# COM_SPI.net
KiCad netlist of a schematic drawn in Altium Designer
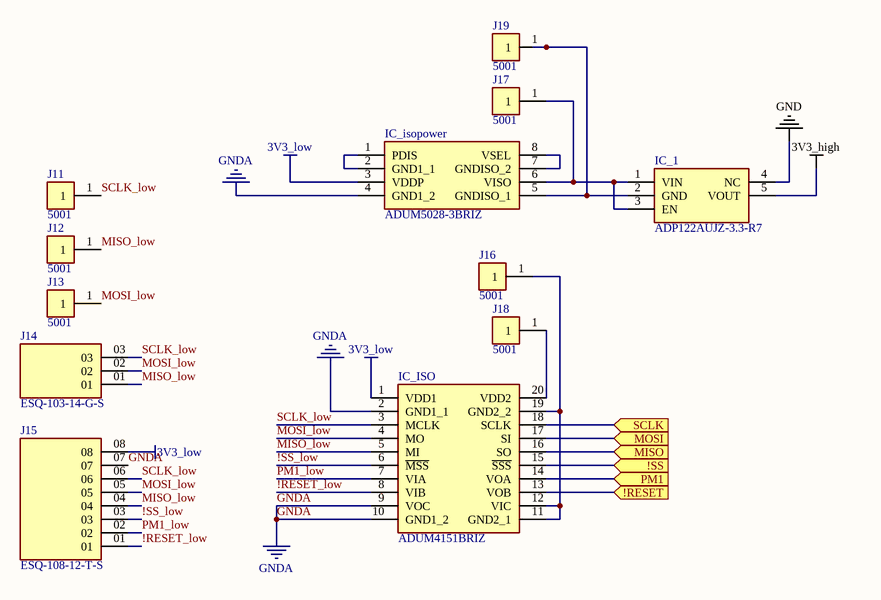
[diagram p0: COM_SPI.SchDoc]

(export (version "E")
  (design (tool "Eeschema 10.0.6"))
  (components
    (comp (ref "IC_1")
      (value "ADP122AUJZ-3.3-R7")
      (footprint "SamacSys:SOT95P280X100-5N")
      (description "Integrated Circuit")
      (fields (field (name "MOUSER PART NUMBER") "584-ADP122AUJZ-3.3R7"))
      (libsource (lib "*") (part "ADP122AUJZ-3.3-R7"))
    )
    (comp (ref "IC_ISO")
      (value "ADUM4151BRIZ")
      (footprint "SamacSys:SOIC127P1031X264-20N")
      (description "Integrated Circuit")
      (fields (field (name "MOUSER PART NUMBER") "584-ADUM4151BRIZ"))
      (libsource (lib "*") (part "ADUM4151BRIZ"))
    )
    (comp (ref "IC_isopower")
      (value "ADUM5028-3BRIZ")
      (footprint "SamacSys:SOIC127P1031X265-8N")
      (description "Integrated Circuit")
      (fields (field (name "MOUSER PART NUMBER") "584-ADUM5028-3BRIZ"))
      (libsource (lib "*") (part "ADUM5028-3BRIZ"))
    )
    (comp (ref "J11")
      (value "5001")
      (footprint "KEYSTONE_5001")
      (description "Conn Test Point SKT 1 POS ST Thru-Hole 1 Port")
      (fields (field (name "MF") "Keystone Electronics Corp."))
      (libsource (lib "5001") (part "5001"))
    )
    (comp (ref "J12")
      (value "5001")
      (footprint "KEYSTONE_5001")
      (description "Conn Test Point SKT 1 POS ST Thru-Hole 1 Port")
      (fields (field (name "MF") "Keystone Electronics Corp."))
      (libsource (lib "5001") (part "5001"))
    )
    (comp (ref "J13")
      (value "5001")
      (footprint "KEYSTONE_5001")
      (description "Conn Test Point SKT 1 POS ST Thru-Hole 1 Port")
      (fields (field (name "MF") "Keystone Electronics Corp."))
      (libsource (lib "5001") (part "5001"))
    )
    (comp (ref "J14")
      (value "ESQ-103-14-G-S")
      (footprint "SAMTEC_ESQ-103-14-G-S")
      (description "Conn Elevated Socket SKT 3 POS 2.54mm Solder ST Top Entry Thru-Hole Bulk")
      (fields (field (name "MF") "Samtec"))
      (libsource (lib "ESQ-103-14-G-S") (part "ESQ-103-14-G-S"))
    )
    (comp (ref "J15")
      (value "ESQ-108-12-T-S")
      (footprint "SAMTEC_ESQ-108-12-T-S")
      (description "Conn Elevated Socket SKT 8 POS 2.54mm Solder ST Top Entry Thru-Hole Tube")
      (fields (field (name "MF") "Samtec"))
      (libsource (lib "ESQ-108-12-T-S") (part "ESQ-108-12-T-S"))
    )
    (comp (ref "J16")
      (value "5001")
      (footprint "KEYSTONE_5001")
      (description "Conn Test Point SKT 1 POS ST Thru-Hole 1 Port")
      (fields (field (name "MF") "Keystone Electronics Corp."))
      (libsource (lib "5001") (part "5001"))
    )
    (comp (ref "J17")
      (value "5001")
      (footprint "KEYSTONE_5001")
      (description "Conn Test Point SKT 1 POS ST Thru-Hole 1 Port")
      (fields (field (name "MF") "Keystone Electronics Corp."))
      (libsource (lib "5001") (part "5001"))
    )
    (comp (ref "J18")
      (value "5001")
      (footprint "KEYSTONE_5001")
      (description "Conn Test Point SKT 1 POS ST Thru-Hole 1 Port")
      (fields (field (name "MF") "Keystone Electronics Corp."))
      (libsource (lib "5001") (part "5001"))
    )
    (comp (ref "J19")
      (value "5001")
      (footprint "KEYSTONE_5001")
      (description "Conn Test Point SKT 1 POS ST Thru-Hole 1 Port")
      (fields (field (name "MF") "Keystone Electronics Corp."))
      (libsource (lib "5001") (part "5001"))
    )
  )
  (nets
    (net (code "1") (name "/!RESET") (class "Default")
      (node (ref "IC_ISO") (pin "13") (pinfunction "VOB_13") (pintype "passive"))
    )
    (net (code "2") (name "/!RESET_low") (class "Default")
      (node (ref "IC_ISO") (pin "8") (pinfunction "VIB_8") (pintype "passive"))
      (node (ref "J15") (pin "01") (pinfunction "01_01") (pintype "passive"))
    )
    (net (code "3") (name "/!SS") (class "Default")
      (node (ref "IC_ISO") (pin "15") (pinfunction "~{SSS}_15") (pintype "passive"))
    )
    (net (code "4") (name "/!SS_low") (class "Default")
      (node (ref "IC_ISO") (pin "6") (pinfunction "~{MSS}_6") (pintype "passive"))
      (node (ref "J15") (pin "03") (pinfunction "03_03") (pintype "passive"))
    )
    (net (code "5") (name "/MISO") (class "Default")
      (node (ref "IC_ISO") (pin "16") (pinfunction "SO_16") (pintype "passive"))
    )
    (net (code "6") (name "/MISO_low") (class "Default")
      (node (ref "IC_ISO") (pin "5") (pinfunction "MI_5") (pintype "passive"))
      (node (ref "J12") (pin "1") (pinfunction "1_1") (pintype "passive"))
      (node (ref "J14") (pin "01") (pinfunction "01_01") (pintype "passive"))
      (node (ref "J15") (pin "04") (pinfunction "04_04") (pintype "passive"))
    )
    (net (code "7") (name "/MOSI") (class "Default")
      (node (ref "IC_ISO") (pin "17") (pinfunction "SI_17") (pintype "passive"))
    )
    (net (code "8") (name "/MOSI_low") (class "Default")
      (node (ref "IC_ISO") (pin "4") (pinfunction "MO_4") (pintype "passive"))
      (node (ref "J13") (pin "1") (pinfunction "1_1") (pintype "passive"))
      (node (ref "J14") (pin "02") (pinfunction "02_02") (pintype "passive"))
      (node (ref "J15") (pin "05") (pinfunction "05_05") (pintype "passive"))
    )
    (net (code "9") (name "/PM1") (class "Default")
      (node (ref "IC_ISO") (pin "14") (pinfunction "VOA_14") (pintype "passive"))
    )
    (net (code "10") (name "/PM1_low") (class "Default")
      (node (ref "IC_ISO") (pin "7") (pinfunction "VIA_7") (pintype "passive"))
      (node (ref "J15") (pin "02") (pinfunction "02_02") (pintype "passive"))
    )
    (net (code "11") (name "/SCLK") (class "Default")
      (node (ref "IC_ISO") (pin "18") (pinfunction "SCLK_18") (pintype "passive"))
    )
    (net (code "12") (name "/SCLK_low") (class "Default")
      (node (ref "IC_ISO") (pin "3") (pinfunction "MCLK_3") (pintype "passive"))
      (node (ref "J11") (pin "1") (pinfunction "1_1") (pintype "passive"))
      (node (ref "J14") (pin "03") (pinfunction "03_03") (pintype "passive"))
      (node (ref "J15") (pin "06") (pinfunction "06_06") (pintype "passive"))
    )
    (net (code "13") (name "3V3_high") (class "Default")
      (node (ref "IC_1") (pin "5") (pinfunction "VOUT_5") (pintype "passive"))
    )
    (net (code "14") (name "3V3_low") (class "Default")
      (node (ref "IC_ISO") (pin "1") (pinfunction "VDD1_1") (pintype "passive"))
      (node (ref "IC_isopower") (pin "3") (pinfunction "VDDP_3") (pintype "passive"))
      (node (ref "J15") (pin "08") (pinfunction "08_08") (pintype "passive"))
    )
    (net (code "15") (name "GND") (class "Default")
      (node (ref "IC_1") (pin "4") (pinfunction "NC_4") (pintype "passive"))
    )
    (net (code "16") (name "GNDA") (class "Default")
      (node (ref "IC_ISO") (pin "10") (pinfunction "GND1_2_10") (pintype "passive"))
      (node (ref "IC_ISO") (pin "2") (pinfunction "GND1_1_2") (pintype "passive"))
      (node (ref "IC_ISO") (pin "9") (pinfunction "VOC_9") (pintype "passive"))
      (node (ref "IC_isopower") (pin "4") (pinfunction "GND1_2_4") (pintype "passive"))
      (node (ref "J15") (pin "07") (pinfunction "07_07") (pintype "passive"))
    )
    (net (code "17") (name "Net-(IC_1-EN)") (class "Default")
      (node (ref "IC_1") (pin "1") (pinfunction "VIN_1") (pintype "passive"))
      (node (ref "IC_1") (pin "3") (pinfunction "EN_3") (pintype "passive"))
      (node (ref "IC_isopower") (pin "6") (pinfunction "VISO_6") (pintype "passive"))
      (node (ref "J17") (pin "1") (pinfunction "1_1") (pintype "passive"))
    )
    (net (code "18") (name "Net-(IC_1-GND)") (class "Default")
      (node (ref "IC_1") (pin "2") (pinfunction "GND_2") (pintype "passive"))
      (node (ref "IC_isopower") (pin "5") (pinfunction "GNDISO_1_5") (pintype "passive"))
      (node (ref "J19") (pin "1") (pinfunction "1_1") (pintype "passive"))
    )
    (net (code "19") (name "Net-(IC_ISO-GND2_1)") (class "Default")
      (node (ref "IC_ISO") (pin "11") (pinfunction "GND2_1_11") (pintype "passive"))
      (node (ref "IC_ISO") (pin "12") (pinfunction "VIC_12") (pintype "passive"))
      (node (ref "IC_ISO") (pin "19") (pinfunction "GND2_2_19") (pintype "passive"))
      (node (ref "J16") (pin "1") (pinfunction "1_1") (pintype "passive"))
    )
    (net (code "20") (name "Net-(IC_ISO-VDD2)") (class "Default")
      (node (ref "IC_ISO") (pin "20") (pinfunction "VDD2_20") (pintype "passive"))
      (node (ref "J18") (pin "1") (pinfunction "1_1") (pintype "passive"))
    )
    (net (code "21") (name "Net-(IC_isopower-GND1_1)") (class "Default")
      (node (ref "IC_isopower") (pin "1") (pinfunction "PDIS_1") (pintype "passive"))
      (node (ref "IC_isopower") (pin "2") (pinfunction "GND1_1_2") (pintype "passive"))
    )
    (net (code "22") (name "Net-(IC_isopower-GNDISO_2)") (class "Default")
      (node (ref "IC_isopower") (pin "7") (pinfunction "GNDISO_2_7") (pintype "passive"))
      (node (ref "IC_isopower") (pin "8") (pinfunction "VSEL_8") (pintype "passive"))
    )
  )
)
